# PowerSupply.net
KiCad netlist of a schematic drawn in Altium Designer
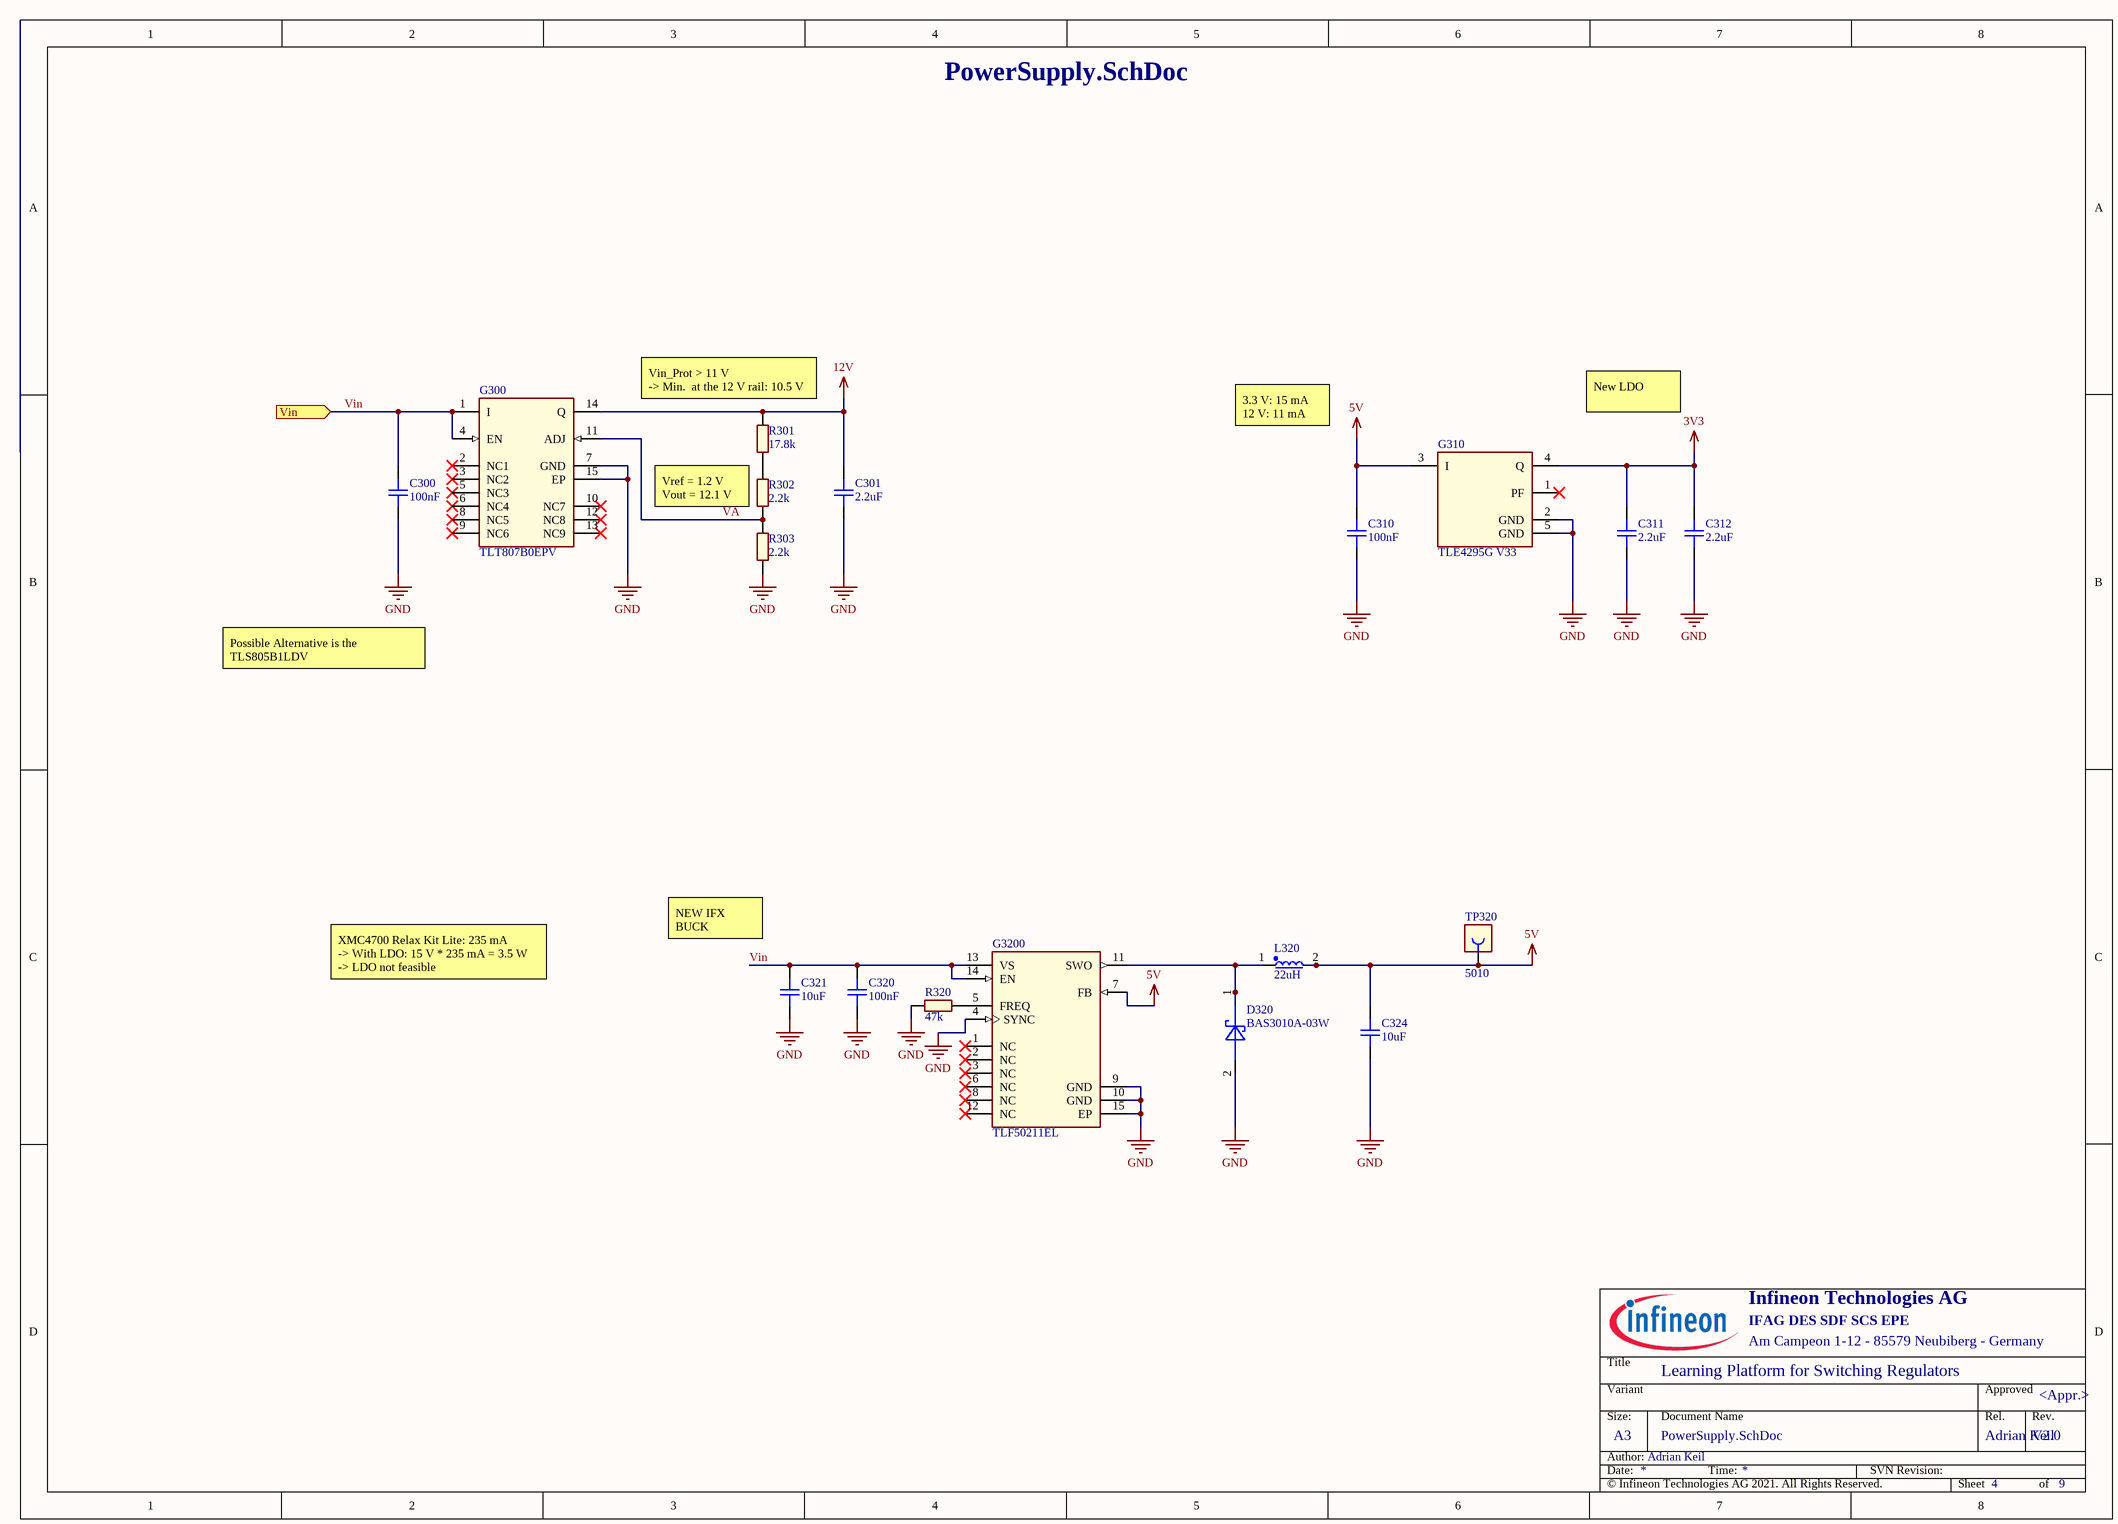
[diagram p0: PowerSupply.SchDoc]

(export (version "E")
  (design (tool "Eeschema 10.0.6"))
  (components
    (comp (ref "C300")
      (value "100nF")
      (footprint "CAPC1608X90N-2")
      (description "CAP / CERA / 100nF / 50V / 10% / X7R (EIA) / -55°C to 125°C / 0603 / SMD / -")
      (fields (field (name "MANUFACTURER") "AVX"))
      (libsource (lib "PCBLibraryData") (part "CAP-SGL-STD-02P_00000001"))
    )
    (comp (ref "C301")
      (value "2.2uF")
      (footprint "CAPC1608X90N-3")
      (description "CAP / CERA / 2.2uF / 25V / 10% / X5R (EIA) / -55°C to 85°C / 0603(1608) / SMD / -")
      (fields (field (name "LEGACY PARTNUMBER") "CAP01010924") (field (name "MANUFACTURER") "MuRata"))
      (libsource (lib "PCBLibraryData") (part "CAP-SGL-STD-02P_00000001"))
    )
    (comp (ref "C310")
      (value "100nF")
      (footprint "CAPC1608X90N-2")
      (description "CAP / CERA / 100nF / 50V / 10% / X7R (EIA) / -55°C to 125°C / 0603 / SMD / -")
      (fields (field (name "MANUFACTURER") "AVX"))
      (libsource (lib "PCBLibraryData") (part "CAP-SGL-STD-02P_00000001"))
    )
    (comp (ref "C311")
      (value "2.2uF")
      (footprint "CAPC1608X90N-3")
      (description "CAP / CERA / 2.2uF / 25V / 10% / X5R (EIA) / -55°C to 85°C / 0603(1608) / SMD / -")
      (fields (field (name "LEGACY PARTNUMBER") "CAP01010924") (field (name "MANUFACTURER") "MuRata"))
      (libsource (lib "PCBLibraryData") (part "CAP-SGL-STD-02P_00000001"))
    )
    (comp (ref "C312")
      (value "2.2uF")
      (footprint "CAPC1608X90N-3")
      (description "CAP / CERA / 2.2uF / 25V / 10% / X5R (EIA) / -55°C to 85°C / 0603(1608) / SMD / -")
      (fields (field (name "LEGACY PARTNUMBER") "CAP01010924") (field (name "MANUFACTURER") "MuRata"))
      (libsource (lib "PCBLibraryData") (part "CAP-SGL-STD-02P_00000001"))
    )
    (comp (ref "C320")
      (value "100nF")
      (footprint "CAPC1608X90N-2")
      (description "CAP / CERA / 100nF / 50V / 10% / X7R (EIA) / -55°C to 125°C / 0603 / SMD / -")
      (fields (field (name "MANUFACTURER") "AVX"))
      (libsource (lib "PCBLibraryData") (part "CAP-SGL-STD-02P_00000001"))
    )
    (comp (ref "C321")
      (value "10uF")
      (footprint "CAPC3216X190N-1")
      (description "CAP / CERA / 10uF / 50V / 20% / X5R (EIA) / -55°C to 85°C / 1206 (3216) / SMD / -")
      (fields (field (name "MANUFACTURER") "Taiyo Yuden"))
      (libsource (lib "PCBLibraryData") (part "CAP-SGL-STD-02P_00000001"))
    )
    (comp (ref "C324")
      (value "10uF")
      (footprint "CAPC3216X190N-1")
      (description "CAP / CERA / 10uF / 50V / 20% / X5R (EIA) / -55°C to 85°C / 1206 (3216) / SMD / -")
      (fields (field (name "MANUFACTURER") "Taiyo Yuden"))
      (libsource (lib "PCBLibraryData") (part "CAP-SGL-STD-02P_00000001"))
    )
    (comp (ref "D320")
      (value "BAS3010A-03W")
      (footprint "SOD2513X110N")
      (description "Medium Power AF Schottky Diode")
      (fields
        (field (name "LEGACY PARTNUMBER") "IFX01400145")
        (field (name "MANUFACTURER") "Infineon Technologies")
      )
      (libsource (lib "PCBLibraryData") (part "d_schottky_a"))
    )
    (comp (ref "G300")
      (value "TLT807B0EPV")
      (footprint "SOP65P600X115-15N")
      (description "Low Dropout Adjustable Standby Voltage Regulator")
      (fields
        (field (name "LEGACY PARTNUMBER") "IFX01401452")
        (field (name "MANUFACTURER") "Infineon Technologies")
      )
      (libsource (lib "PCBLibraryData") (part "TLT807B0EPV"))
    )
    (comp (ref "G310")
      (value "TLE4295G V33")
      (footprint "IFX-PG-SCT595-5-2")
      (fields (field (name "MANUFACTURER") "Infineon Technologies"))
      (libsource (lib "PCBLibraryData") (part "TLE4285 G"))
    )
    (comp (ref "G3200")
      (value "TLF50211EL")
      (footprint "SOP65P600X170-15N")
      (description "2.2 MHz Step-Down Regulator 500 mA, 5 V, low quiescent current")
      (fields (field (name "MANUFACTURER") "Infineon Technologies"))
      (libsource (lib "PCBLibraryData") (part "IFX90121EL"))
    )
    (comp (ref "L320")
      (value "22uH")
      (footprint "IND-SMD-74404064220")
      (fields (field (name "MANUFACTURER") "Wurth Elektronik"))
      (libsource (lib "PCBLibraryData") (part "IND-SGL-STD-WDG-COR-02P_0000002B"))
    )
    (comp (ref "R301")
      (value "17.8k")
      (footprint "RESC1608X60N")
      (fields (field (name "MANUFACTURER") "Multicomp"))
      (libsource (lib "") (part "RES-SGL-STD-02P_00000006_1"))
    )
    (comp (ref "R302")
      (value "2.2k")
      (footprint "RESC1609X50N")
      (description "RES / STD / 2.2k / 100mW / 1% / 100ppm/K / -55°C to 155°C / 0603 / SMD / -")
      (fields (field (name "LEGACY PARTNUMBER") "RES01801179") (field (name "MANUFACTURER") "Vishay"))
      (libsource (lib "PCBLibraryData") (part "RES-SGL-STD-02P_00000006"))
    )
    (comp (ref "R303")
      (value "2.2k")
      (footprint "RESC1609X50N")
      (description "RES / STD / 2.2k / 100mW / 1% / 100ppm/K / -55°C to 155°C / 0603 / SMD / -")
      (fields (field (name "LEGACY PARTNUMBER") "RES01801179") (field (name "MANUFACTURER") "Vishay"))
      (libsource (lib "PCBLibraryData") (part "RES-SGL-STD-02P_00000006"))
    )
    (comp (ref "R320")
      (value "47k")
      (footprint "RESC1609X50N")
      (description "RES / STD / 47k / 100mW / 1% / 100ppm/K / -55°C to 155°C / 0603 / SMD / -")
      (fields (field (name "LEGACY PARTNUMBER") "RES01801333") (field (name "MANUFACTURER") "Vishay"))
      (libsource (lib "") (part "RES-SGL-STD-02P_00000006_2"))
    )
    (comp (ref "TP320")
      (value "5010")
      (footprint "CON-THT-TP-5010")
      (description "PC Test Point-Multipurpose THT, Red")
      (fields
        (field (name "LEGACY PARTNUMBER") "CON01500529")
        (field (name "MANUFACTURER") "Keystone Electronics Corp.")
      )
      (libsource (lib "PCBLibraryData") (part "connector_1_f"))
    )
  )
  (nets
    (net (code "1") (name "/VA") (class "Default")
      (node (ref "G300") (pin "11") (pinfunction "ADJ_11") (pintype "input"))
      (node (ref "R302") (pin "1") (pinfunction "1_1") (pintype "passive"))
      (node (ref "R303") (pin "2") (pinfunction "2_2") (pintype "passive"))
    )
    (net (code "2") (name "/Vin") (class "Default")
      (node (ref "C300") (pin "2") (pinfunction "2_2") (pintype "passive"))
      (node (ref "C320") (pin "2") (pinfunction "2_2") (pintype "passive"))
      (node (ref "C321") (pin "2") (pinfunction "2_2") (pintype "passive"))
      (node (ref "G300") (pin "1") (pinfunction "I_1") (pintype "power_in"))
      (node (ref "G300") (pin "4") (pinfunction "EN_4") (pintype "input"))
      (node (ref "G3200") (pin "13") (pinfunction "VS_13") (pintype "power_in"))
      (node (ref "G3200") (pin "14") (pinfunction "EN_14") (pintype "input"))
    )
    (net (code "3") (name "3V3") (class "Default")
      (node (ref "C311") (pin "2") (pinfunction "2_2") (pintype "passive"))
      (node (ref "C312") (pin "2") (pinfunction "2_2") (pintype "passive"))
      (node (ref "G310") (pin "4") (pinfunction "Q_4") (pintype "power_in"))
    )
    (net (code "4") (name "5V") (class "Default")
      (node (ref "C310") (pin "2") (pinfunction "2_2") (pintype "passive"))
      (node (ref "C324") (pin "2") (pinfunction "2_2") (pintype "passive"))
      (node (ref "G310") (pin "3") (pinfunction "I_3") (pintype "power_in"))
      (node (ref "G3200") (pin "7") (pinfunction "FB_7") (pintype "input"))
      (node (ref "L320") (pin "2") (pinfunction "2_2") (pintype "passive"))
      (node (ref "TP320") (pin "1") (pinfunction "1_1") (pintype "passive"))
    )
    (net (code "5") (name "12V") (class "Default")
      (node (ref "C301") (pin "2") (pinfunction "2_2") (pintype "passive"))
      (node (ref "G300") (pin "14") (pinfunction "Q_14") (pintype "power_in"))
      (node (ref "R301") (pin "1") (pinfunction "1_1") (pintype "passive"))
    )
    (net (code "6") (name "GND") (class "Default")
      (node (ref "C300") (pin "1") (pinfunction "1_1") (pintype "passive"))
      (node (ref "C301") (pin "1") (pinfunction "1_1") (pintype "passive"))
      (node (ref "C310") (pin "1") (pinfunction "1_1") (pintype "passive"))
      (node (ref "C311") (pin "1") (pinfunction "1_1") (pintype "passive"))
      (node (ref "C312") (pin "1") (pinfunction "1_1") (pintype "passive"))
      (node (ref "C320") (pin "1") (pinfunction "1_1") (pintype "passive"))
      (node (ref "C321") (pin "1") (pinfunction "1_1") (pintype "passive"))
      (node (ref "C324") (pin "1") (pinfunction "1_1") (pintype "passive"))
      (node (ref "D320") (pin "2") (pinfunction "Anode_2") (pintype "passive"))
      (node (ref "G300") (pin "15") (pinfunction "EP_15") (pintype "power_in"))
      (node (ref "G300") (pin "7") (pinfunction "GND_7") (pintype "power_in"))
      (node (ref "G310") (pin "2") (pinfunction "GND_2") (pintype "power_in"))
      (node (ref "G310") (pin "5") (pinfunction "GND_5") (pintype "power_in"))
      (node (ref "G3200") (pin "10") (pinfunction "GND_10") (pintype "power_in"))
      (node (ref "G3200") (pin "15") (pinfunction "EP_15") (pintype "power_in"))
      (node (ref "G3200") (pin "4") (pinfunction "SYNC_4") (pintype "input"))
      (node (ref "G3200") (pin "9") (pinfunction "GND_9") (pintype "power_in"))
      (node (ref "R303") (pin "1") (pinfunction "1_1") (pintype "passive"))
      (node (ref "R320") (pin "2") (pinfunction "2_2") (pintype "passive"))
    )
    (net (code "7") (name "Net-(D320-Cathode)") (class "Default")
      (node (ref "D320") (pin "1") (pinfunction "Cathode_1") (pintype "passive"))
      (node (ref "G3200") (pin "11") (pinfunction "SWO_11") (pintype "output"))
      (node (ref "L320") (pin "1") (pinfunction "1_1") (pintype "passive"))
    )
    (net (code "8") (name "Net-(G3200-FREQ)") (class "Default")
      (node (ref "G3200") (pin "5") (pinfunction "FREQ_5") (pintype "passive"))
      (node (ref "R320") (pin "1") (pinfunction "1_1") (pintype "passive"))
    )
    (net (code "9") (name "Net-(R301-Pad2)") (class "Default")
      (node (ref "R301") (pin "2") (pinfunction "2_2") (pintype "passive"))
      (node (ref "R302") (pin "2") (pinfunction "2_2") (pintype "passive"))
    )
    (net (code "10") (name "unconnected-(G300-NC1-Pad2)") (class "Default")
      (node (ref "G300") (pin "2") (pinfunction "NC1_2") (pintype "passive+no_connect"))
    )
    (net (code "11") (name "unconnected-(G300-NC2-Pad3)") (class "Default")
      (node (ref "G300") (pin "3") (pinfunction "NC2_3") (pintype "passive+no_connect"))
    )
    (net (code "12") (name "unconnected-(G300-NC3-Pad5)") (class "Default")
      (node (ref "G300") (pin "5") (pinfunction "NC3_5") (pintype "passive+no_connect"))
    )
    (net (code "13") (name "unconnected-(G300-NC4-Pad6)") (class "Default")
      (node (ref "G300") (pin "6") (pinfunction "NC4_6") (pintype "passive+no_connect"))
    )
    (net (code "14") (name "unconnected-(G300-NC5-Pad8)") (class "Default")
      (node (ref "G300") (pin "8") (pinfunction "NC5_8") (pintype "passive+no_connect"))
    )
    (net (code "15") (name "unconnected-(G300-NC6-Pad9)") (class "Default")
      (node (ref "G300") (pin "9") (pinfunction "NC6_9") (pintype "passive+no_connect"))
    )
    (net (code "16") (name "unconnected-(G300-NC7-Pad10)") (class "Default")
      (node (ref "G300") (pin "10") (pinfunction "NC7_10") (pintype "passive+no_connect"))
    )
    (net (code "17") (name "unconnected-(G300-NC8-Pad12)") (class "Default")
      (node (ref "G300") (pin "12") (pinfunction "NC8_12") (pintype "passive+no_connect"))
    )
    (net (code "18") (name "unconnected-(G300-NC9-Pad13)") (class "Default")
      (node (ref "G300") (pin "13") (pinfunction "NC9_13") (pintype "passive+no_connect"))
    )
    (net (code "19") (name "unconnected-(G310-PF-Pad1)") (class "Default")
      (node (ref "G310") (pin "1") (pinfunction "PF_1") (pintype "power_in+no_connect"))
    )
    (net (code "20") (name "unconnected-(G3200-NC-Pad1)") (class "Default")
      (node (ref "G3200") (pin "1") (pinfunction "NC_1") (pintype "passive+no_connect"))
    )
    (net (code "21") (name "unconnected-(G3200-NC-Pad2)") (class "Default")
      (node (ref "G3200") (pin "2") (pinfunction "NC_2") (pintype "passive+no_connect"))
    )
    (net (code "22") (name "unconnected-(G3200-NC-Pad3)") (class "Default")
      (node (ref "G3200") (pin "3") (pinfunction "NC_3") (pintype "passive+no_connect"))
    )
    (net (code "23") (name "unconnected-(G3200-NC-Pad6)") (class "Default")
      (node (ref "G3200") (pin "6") (pinfunction "NC_6") (pintype "passive+no_connect"))
    )
    (net (code "24") (name "unconnected-(G3200-NC-Pad8)") (class "Default")
      (node (ref "G3200") (pin "8") (pinfunction "NC_8") (pintype "passive+no_connect"))
    )
    (net (code "25") (name "unconnected-(G3200-NC-Pad12)") (class "Default")
      (node (ref "G3200") (pin "12") (pinfunction "NC_12") (pintype "passive+no_connect"))
    )
  )
)
